# MCU.net
KiCad netlist of a schematic drawn in Altium Designer
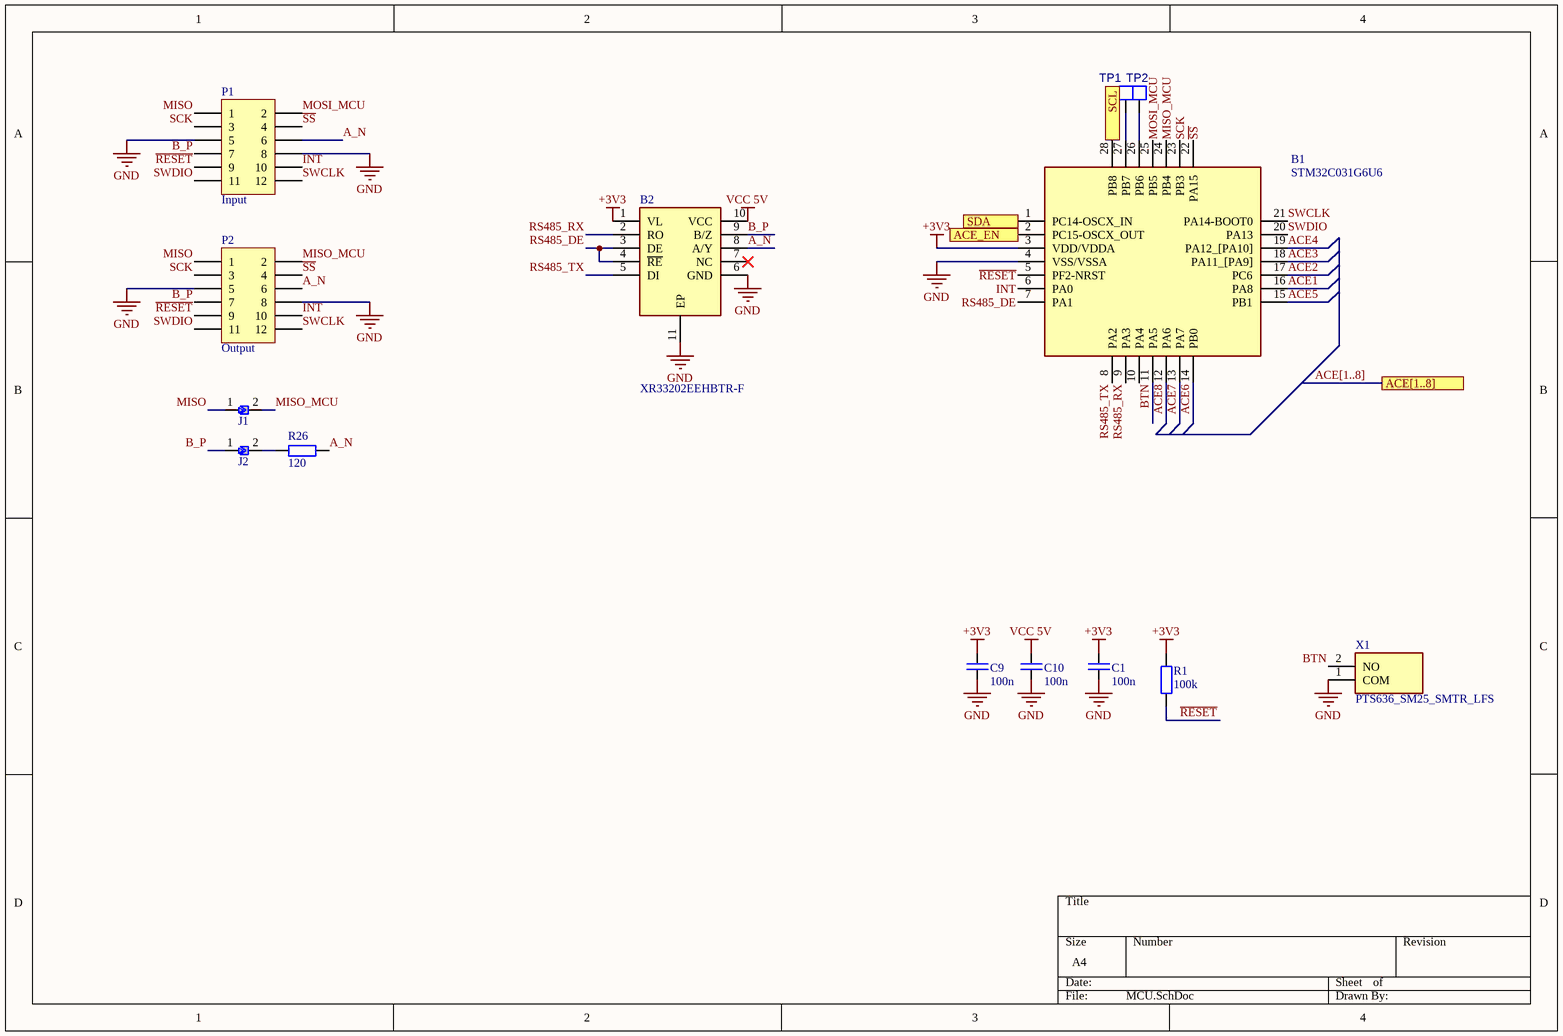
[diagram p0: MCU.SchDoc]

(export (version "E")
  (design (tool "Eeschema 10.0.6"))
  (components
    (comp (ref "B1")
      (value "STM32C031G6U6")
      (footprint "QFN50P400X400X60-28N-D")
      (fields (field (name "MOUSER PART NUMBER") "511-STM32C031G6U6"))
      (libsource (lib "components_library") (part "STM32C031G6U6"))
    )
    (comp (ref "B2")
      (value "XR33202EEHBTR-F")
      (footprint "SON50P300X300X80-11N-D")
      (description "RS-422/RS-485 Interface IC Wide Supply Trans with I/O Interface")
      (fields (field (name "MOUSER PART NUMBER") "701-XR33202EEHBTR-F"))
      (libsource (lib "components_library") (part "XR33202EEHBTR-F"))
    )
    (comp (ref "C1")
      (value "100n")
      (footprint "R1005_0402i_L")
      (description "Capacitor")
      (libsource (lib "General") (part "C"))
    )
    (comp (ref "C9")
      (value "100n")
      (footprint "R1005_0402i_L")
      (description "Capacitor")
      (libsource (lib "General") (part "C"))
    )
    (comp (ref "C10")
      (value "100n")
      (footprint "R1005_0402i_L")
      (description "Capacitor")
      (libsource (lib "General") (part "C"))
    )
    (comp (ref "J1")
      (value "solder_jumper")
      (footprint "solder_jumper_triangle")
      (libsource (lib "components_library") (part "solder_jumper"))
    )
    (comp (ref "J2")
      (value "solder_jumper")
      (footprint "solder_jumper_triangle")
      (libsource (lib "components_library") (part "solder_jumper"))
    )
    (comp (ref "P1")
      (value "Input")
      (footprint "1.27mm SMD conn")
      (description "Header, 6-Pin, Dual row")
      (fields (field (name "PUBLISHER") "Altium Limited"))
      (libsource (lib "Miscellaneous Connectors") (part "Header 6X2"))
    )
    (comp (ref "P2")
      (value "Output")
      (footprint "1.27mm SMD conn")
      (description "Header, 6-Pin, Dual row")
      (fields (field (name "PUBLISHER") "Altium Limited"))
      (libsource (lib "Miscellaneous Connectors") (part "Header 6X2"))
    )
    (comp (ref "R1")
      (value "100k")
      (footprint "R1005_0402i_L")
      (description "R")
      (libsource (lib "General") (part "R"))
    )
    (comp (ref "R26")
      (value "120")
      (footprint "R1005_0402i_L")
      (description "R")
      (libsource (lib "General") (part "R"))
    )
    (comp (ref "TP1") (value "PAD") (footprint "PAD") (libsource (lib "General") (part "PAD")))
    (comp (ref "TP2") (value "PAD") (footprint "PAD") (libsource (lib "General") (part "PAD")))
    (comp (ref "X1")
      (value "PTS636_SM25_SMTR_LFS")
      (footprint "PTS636SM25SMTRLFS")
      (description "Tactile Switches Tact 50mA 12VDC, 6.0x3.5, 2.5mm H, 180gf, G leads, No ground pin, White Actuator")
      (fields
        (field (name "MOUSER PART NUMBER") "611-PTS636SM25SMTRLF")
        (field (name "MANUFACTURER_PART_NUMBER") "PTS636 SM25 SMTR LFS")
      )
      (libsource (lib "components_library") (part "PTS636_SM25_SMTR_LFS"))
    )
  )
  (nets
    (net (code "1") (name "+3V3") (class "Default")
      (node (ref "B1") (pin "3") (pinfunction "VDD/VDDA_3") (pintype "passive"))
      (node (ref "B2") (pin "1") (pinfunction "VL_1") (pintype "passive"))
      (node (ref "C1") (pin "1") (pinfunction "1_1") (pintype "passive"))
      (node (ref "C9") (pin "1") (pinfunction "1_1") (pintype "passive"))
      (node (ref "R1") (pin "1") (pintype "passive"))
    )
    (net (code "2") (name "/ACE1") (class "Default")
      (node (ref "B1") (pin "16") (pinfunction "PA8_16") (pintype "passive"))
    )
    (net (code "3") (name "/ACE2") (class "Default")
      (node (ref "B1") (pin "17") (pinfunction "PC6_17") (pintype "passive"))
    )
    (net (code "4") (name "/ACE3") (class "Default")
      (node (ref "B1") (pin "18") (pinfunction "PA11_[PA9]_18") (pintype "passive"))
    )
    (net (code "5") (name "/ACE4") (class "Default")
      (node (ref "B1") (pin "19") (pinfunction "PA12_[PA10]_19") (pintype "passive"))
    )
    (net (code "6") (name "/ACE5") (class "Default")
      (node (ref "B1") (pin "15") (pinfunction "PB1_15") (pintype "passive"))
    )
    (net (code "7") (name "/ACE6") (class "Default")
      (node (ref "B1") (pin "14") (pinfunction "PB0_14") (pintype "passive"))
    )
    (net (code "8") (name "/ACE7") (class "Default")
      (node (ref "B1") (pin "13") (pinfunction "PA7_13") (pintype "passive"))
    )
    (net (code "9") (name "/ACE8") (class "Default")
      (node (ref "B1") (pin "12") (pinfunction "PA6_12") (pintype "passive"))
    )
    (net (code "11") (name "/ACE_EN") (class "Default")
      (node (ref "B1") (pin "2") (pinfunction "PC15-OSCX_OUT_2") (pintype "passive"))
    )
    (net (code "12") (name "/A_N") (class "Default")
      (node (ref "B2") (pin "8") (pinfunction "A/Y_8") (pintype "passive"))
      (node (ref "P1") (pin "6") (pinfunction "6_6") (pintype "passive"))
      (node (ref "P2") (pin "6") (pinfunction "6_6") (pintype "passive"))
      (node (ref "R26") (pin "2") (pintype "passive"))
    )
    (net (code "13") (name "/BTN") (class "Default")
      (node (ref "B1") (pin "11") (pinfunction "PA5_11") (pintype "passive"))
      (node (ref "X1") (pin "2") (pinfunction "NO_2") (pintype "passive"))
    )
    (net (code "14") (name "/B_P") (class "Default")
      (node (ref "B2") (pin "9") (pinfunction "B/Z_9") (pintype "passive"))
      (node (ref "J2") (pin "1") (pintype "passive"))
      (node (ref "P1") (pin "7") (pinfunction "7_7") (pintype "passive"))
      (node (ref "P2") (pin "7") (pinfunction "7_7") (pintype "passive"))
    )
    (net (code "15") (name "/INT") (class "Default")
      (node (ref "B1") (pin "6") (pinfunction "PA0_6") (pintype "passive"))
      (node (ref "P1") (pin "10") (pinfunction "10_10") (pintype "passive"))
      (node (ref "P2") (pin "10") (pinfunction "10_10") (pintype "passive"))
    )
    (net (code "16") (name "/MISO") (class "Default")
      (node (ref "J1") (pin "1") (pintype "passive"))
      (node (ref "P1") (pin "1") (pinfunction "1_1") (pintype "passive"))
      (node (ref "P2") (pin "1") (pinfunction "1_1") (pintype "passive"))
    )
    (net (code "17") (name "/MISO_MCU") (class "Default")
      (node (ref "B1") (pin "24") (pinfunction "PB4_24") (pintype "passive"))
      (node (ref "J1") (pin "2") (pintype "passive"))
      (node (ref "P2") (pin "2") (pinfunction "2_2") (pintype "passive"))
    )
    (net (code "18") (name "/MOSI_MCU") (class "Default")
      (node (ref "B1") (pin "25") (pinfunction "PB5_25") (pintype "passive"))
      (node (ref "P1") (pin "2") (pinfunction "2_2") (pintype "passive"))
    )
    (net (code "19") (name "/RS485_DE") (class "Default")
      (node (ref "B1") (pin "7") (pinfunction "PA1_7") (pintype "passive"))
      (node (ref "B2") (pin "3") (pinfunction "DE_3") (pintype "passive"))
      (node (ref "B2") (pin "4") (pinfunction "~{RE}_4") (pintype "passive"))
    )
    (net (code "20") (name "/RS485_RX") (class "Default")
      (node (ref "B1") (pin "9") (pinfunction "PA3_9") (pintype "passive"))
      (node (ref "B2") (pin "2") (pinfunction "RO_2") (pintype "passive"))
    )
    (net (code "21") (name "/RS485_TX") (class "Default")
      (node (ref "B1") (pin "8") (pinfunction "PA2_8") (pintype "passive"))
      (node (ref "B2") (pin "5") (pinfunction "DI_5") (pintype "passive"))
    )
    (net (code "22") (name "/SCK") (class "Default")
      (node (ref "B1") (pin "23") (pinfunction "PB3_23") (pintype "passive"))
      (node (ref "P1") (pin "3") (pinfunction "3_3") (pintype "passive"))
      (node (ref "P2") (pin "3") (pinfunction "3_3") (pintype "passive"))
    )
    (net (code "23") (name "/SCL") (class "Default")
      (node (ref "B1") (pin "28") (pinfunction "PB8_28") (pintype "passive"))
    )
    (net (code "24") (name "/SDA") (class "Default")
      (node (ref "B1") (pin "1") (pinfunction "PC14-OSCX_IN_1") (pintype "passive"))
    )
    (net (code "25") (name "/SWCLK") (class "Default")
      (node (ref "B1") (pin "21") (pinfunction "PA14-BOOT0_21") (pintype "passive"))
      (node (ref "P1") (pin "12") (pinfunction "12_12") (pintype "passive"))
      (node (ref "P2") (pin "12") (pinfunction "12_12") (pintype "passive"))
    )
    (net (code "26") (name "/SWDIO") (class "Default")
      (node (ref "B1") (pin "20") (pinfunction "PA13_20") (pintype "passive"))
      (node (ref "P1") (pin "11") (pinfunction "11_11") (pintype "passive"))
      (node (ref "P2") (pin "11") (pinfunction "11_11") (pintype "passive"))
    )
    (net (code "27") (name "/~{RESET}") (class "Default")
      (node (ref "B1") (pin "5") (pinfunction "PF2-NRST_5") (pintype "passive"))
      (node (ref "P1") (pin "9") (pinfunction "9_9") (pintype "passive"))
      (node (ref "P2") (pin "9") (pinfunction "9_9") (pintype "passive"))
      (node (ref "R1") (pin "2") (pintype "passive"))
    )
    (net (code "28") (name "/~{SS}") (class "Default")
      (node (ref "B1") (pin "22") (pinfunction "PA15_22") (pintype "passive"))
      (node (ref "P1") (pin "4") (pinfunction "4_4") (pintype "passive"))
      (node (ref "P2") (pin "4") (pinfunction "4_4") (pintype "passive"))
    )
    (net (code "29") (name "GND") (class "Default")
      (node (ref "B1") (pin "4") (pinfunction "VSS/VSSA_4") (pintype "passive"))
      (node (ref "B2") (pin "11") (pinfunction "EP_11") (pintype "passive"))
      (node (ref "B2") (pin "6") (pinfunction "GND_6") (pintype "passive"))
      (node (ref "C1") (pin "2") (pinfunction "2_2") (pintype "passive"))
      (node (ref "C10") (pin "2") (pinfunction "2_2") (pintype "passive"))
      (node (ref "C9") (pin "2") (pinfunction "2_2") (pintype "passive"))
      (node (ref "P1") (pin "5") (pinfunction "5_5") (pintype "passive"))
      (node (ref "P1") (pin "8") (pinfunction "8_8") (pintype "passive"))
      (node (ref "P2") (pin "5") (pinfunction "5_5") (pintype "passive"))
      (node (ref "P2") (pin "8") (pinfunction "8_8") (pintype "passive"))
      (node (ref "X1") (pin "1") (pinfunction "COM_1") (pintype "passive"))
    )
    (net (code "30") (name "Net-(B1-PB6)") (class "Default")
      (node (ref "B1") (pin "26") (pinfunction "PB6_26") (pintype "passive"))
      (node (ref "TP2") (pin "1") (pinfunction "1_1") (pintype "passive"))
    )
    (net (code "31") (name "Net-(B1-PB7)") (class "Default")
      (node (ref "B1") (pin "27") (pinfunction "PB7_27") (pintype "passive"))
      (node (ref "TP1") (pin "1") (pinfunction "1_1") (pintype "passive"))
    )
    (net (code "32") (name "Net-(J2-Pad2)") (class "Default")
      (node (ref "J2") (pin "2") (pintype "passive"))
      (node (ref "R26") (pin "1") (pintype "passive"))
    )
    (net (code "33") (name "VCC 5V") (class "Default")
      (node (ref "B2") (pin "10") (pinfunction "VCC_10") (pintype "passive"))
      (node (ref "C10") (pin "1") (pinfunction "1_1") (pintype "passive"))
    )
    (net (code "34") (name "unconnected-(B1-PA4-Pad10)") (class "Default")
      (node (ref "B1") (pin "10") (pinfunction "PA4_10") (pintype "passive"))
    )
    (net (code "35") (name "unconnected-(B2-NC-Pad7)") (class "Default")
      (node (ref "B2") (pin "7") (pinfunction "NC_7") (pintype "passive+no_connect"))
    )
  )
)
